# Verification_system_schematics.net
KiCad netlist of a schematic drawn in EasyEDA
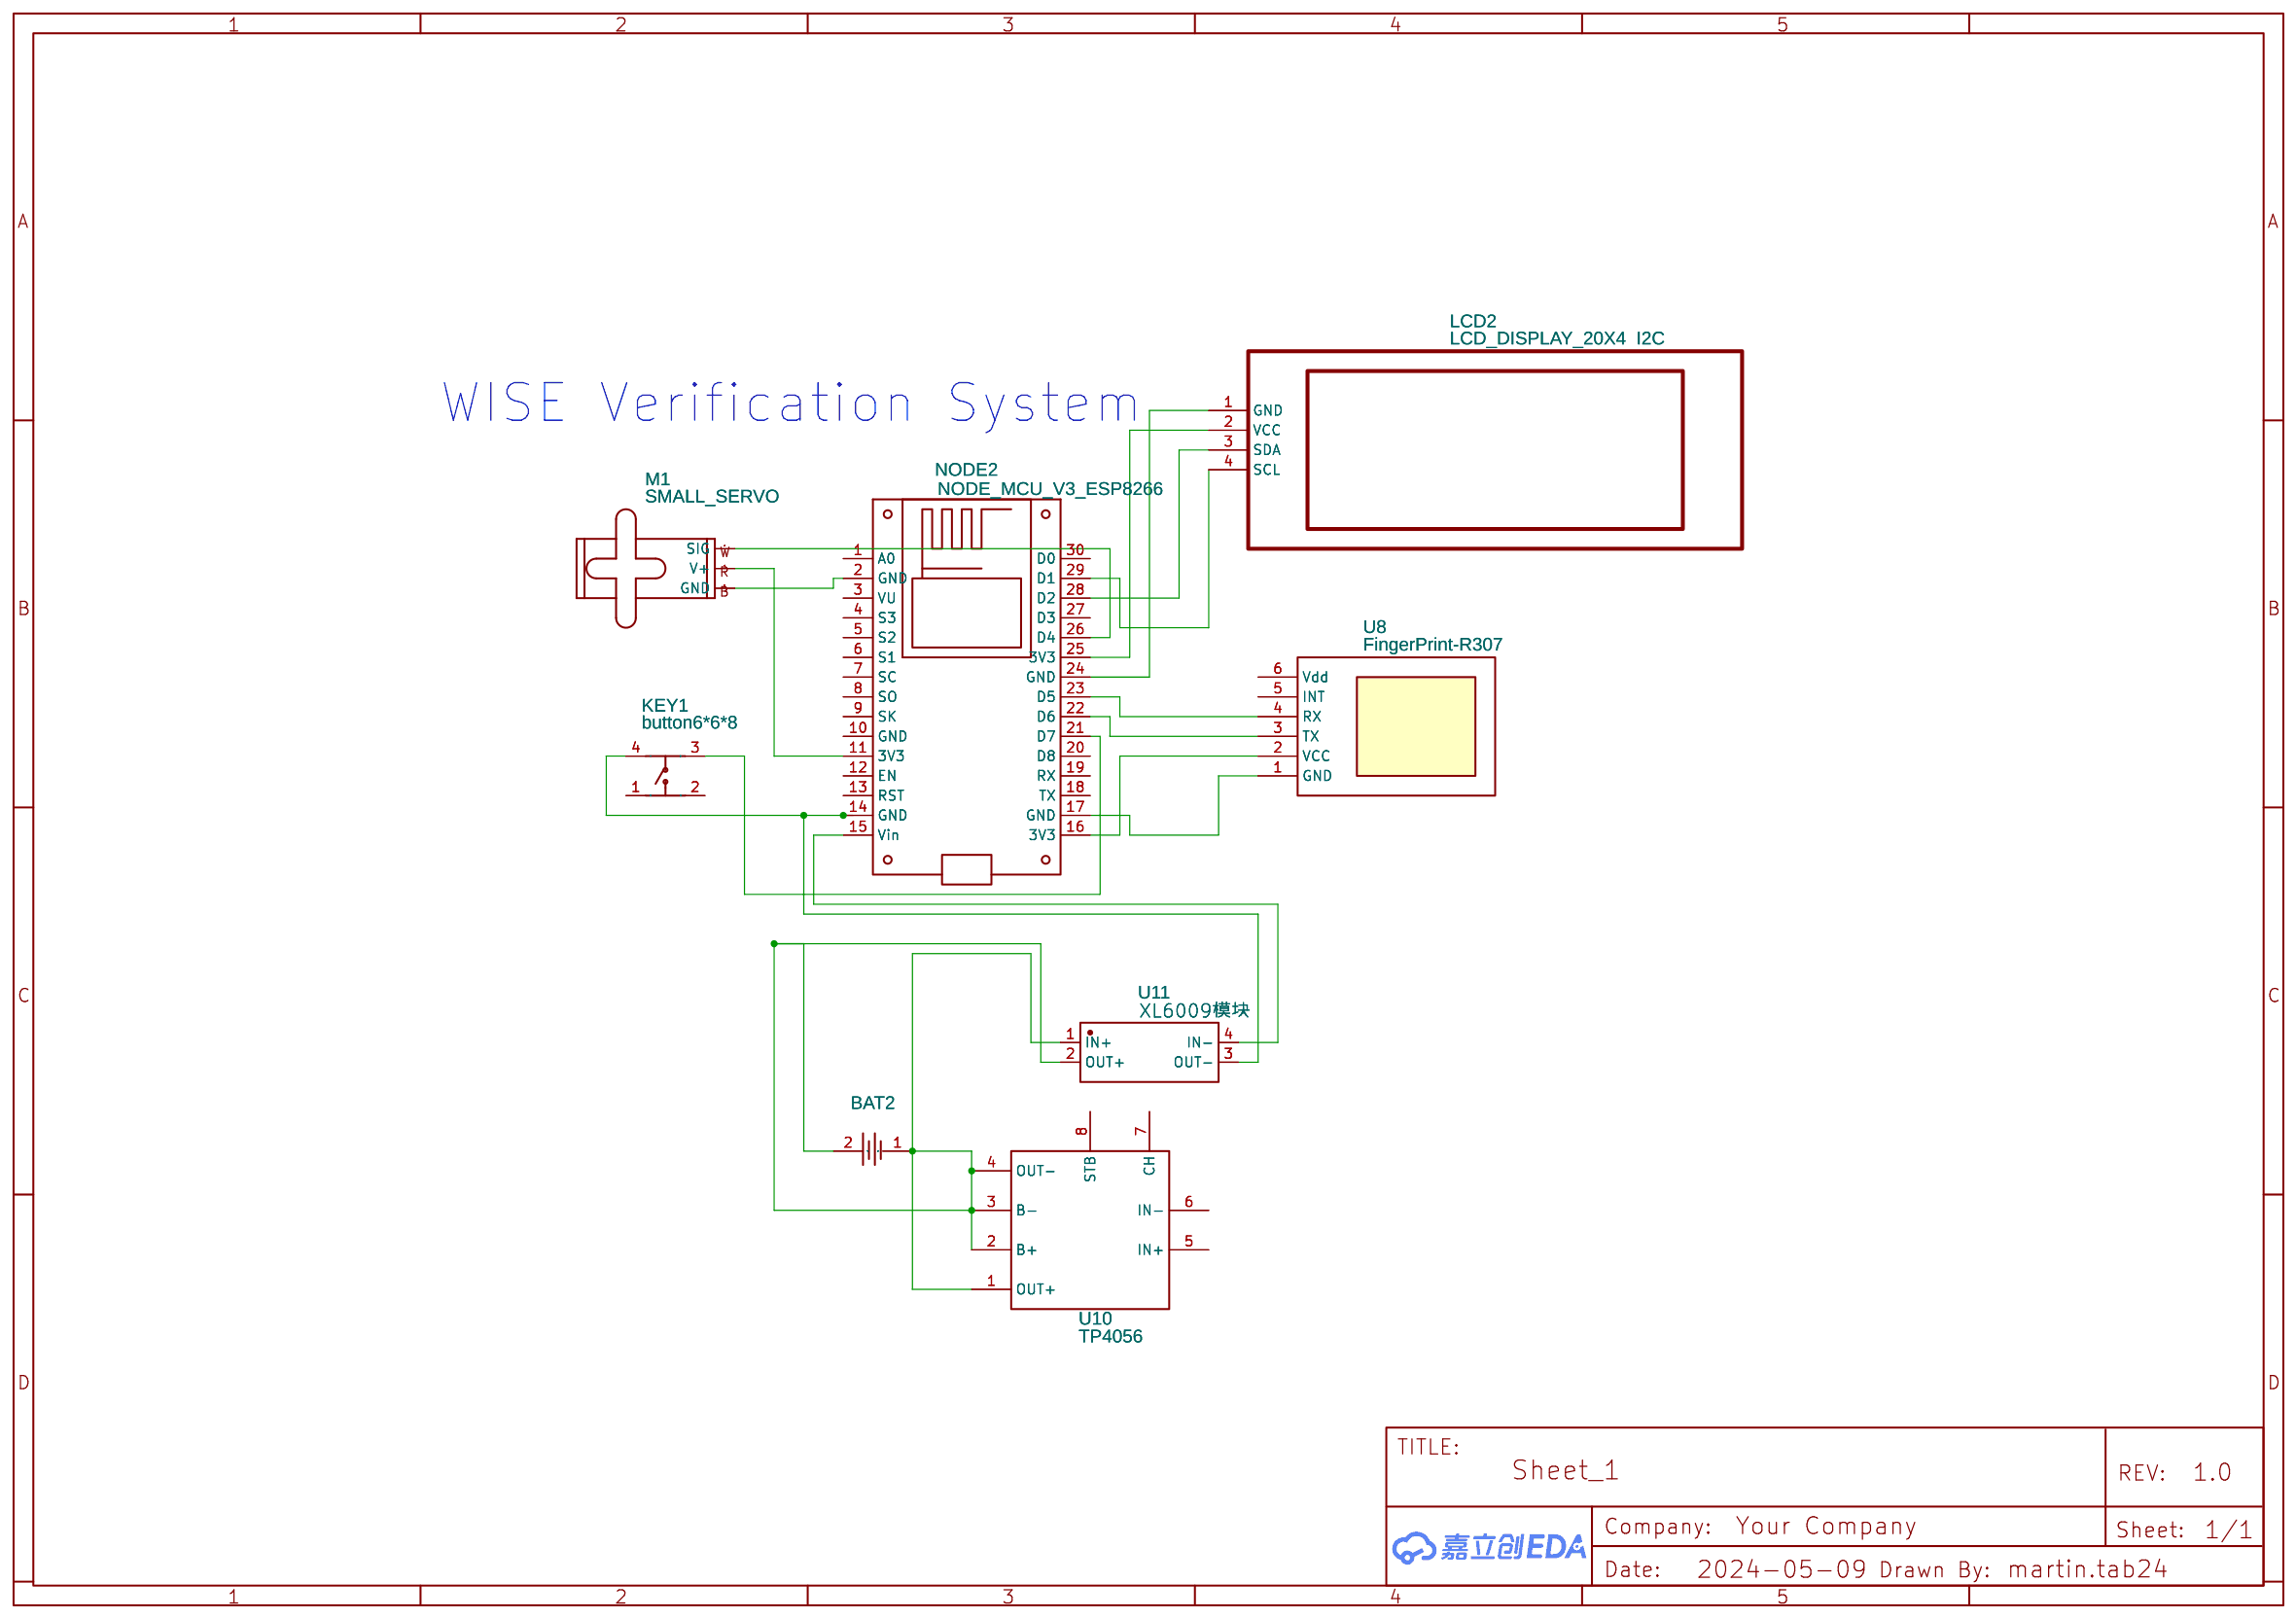
[diagram p0: schematic sheet]

(export (version "E")
  (design (tool "Eeschema 10.0.6"))
  (components
    (comp (ref "BAT2")
      (value "BH-18650-B6AA002")
      (fields (field (name "Manufacturer") "MYOUNG(美阳)"))
      (libsource (lib "") (part "BH-18650-B6AA002"))
    )
    (comp (ref "KEY1")
      (value "button6*6*8")
      (fields (field (name "Manufacturer") "ReliaPro"))
      (libsource (lib "") (part "button6*6*8"))
    )
    (comp (ref "LCD2") (value "LCD_DISPLAY_20X4  I2C") (libsource (lib "") (part "LCD_DISPLAY_20X4  I2C")))
    (comp (ref "M1") (value "SMALL_SERVO") (libsource (lib "") (part "SMALL_SERVO")))
    (comp (ref "NODE2") (value "NODE_MCU_V3_ESP8266") (libsource (lib "") (part "NODE_MCU_V3_ESP8266")))
    (comp (ref "U8")
      (value "FingerPrint-R307")
      (fields (field (name "Manufacturer Part") "R307"))
      (libsource (lib "") (part "FingerPrint-R307"))
    )
    (comp (ref "U10")
      (value "TP4056")
      (fields (field (name "BOM_Manufacturer Part") "New SchematicLib"))
      (libsource (lib "") (part "TP4056"))
    )
    (comp (ref "U11")
      (value "XL6009模块")
      (fields (field (name "Manufacturer Part") "xl6009模块"))
      (libsource (lib "") (part "XL6009模块"))
    )
  )
  (nets
    (net (code "1") (name "Net-(LCD2-GND)") (class "Default")
      (node (ref "LCD2") (pin "1") (pinfunction "GND_1") (pintype "passive"))
      (node (ref "NODE2") (pin "24") (pinfunction "GND_24") (pintype "unspecified"))
    )
    (net (code "2") (name "Net-(LCD2-SCL)") (class "Default")
      (node (ref "LCD2") (pin "4") (pinfunction "SCL_4") (pintype "passive"))
      (node (ref "NODE2") (pin "29") (pinfunction "D1_29") (pintype "unspecified"))
    )
    (net (code "3") (name "Net-(LCD2-SDA)") (class "Default")
      (node (ref "LCD2") (pin "3") (pinfunction "SDA_3") (pintype "passive"))
      (node (ref "NODE2") (pin "28") (pinfunction "D2_28") (pintype "unspecified"))
    )
    (net (code "4") (name "Net-(LCD2-VCC)") (class "Default")
      (node (ref "LCD2") (pin "2") (pinfunction "VCC_2") (pintype "passive"))
      (node (ref "NODE2") (pin "25") (pinfunction "3V3_25") (pintype "unspecified"))
    )
    (net (code "5") (name "Net-(M1-GND)") (class "Default")
      (node (ref "M1") (pin "3") (pinfunction "GND_3") (pintype "unspecified"))
      (node (ref "NODE2") (pin "2") (pinfunction "GND_2") (pintype "unspecified"))
    )
    (net (code "6") (name "Net-(M1-SIG)") (class "Default")
      (node (ref "M1") (pin "1") (pinfunction "SIG_1") (pintype "unspecified"))
      (node (ref "NODE2") (pin "26") (pinfunction "D4_26") (pintype "unspecified"))
    )
    (net (code "7") (name "Net-(M1-V+)") (class "Default")
      (node (ref "M1") (pin "2") (pinfunction "V+_2") (pintype "unspecified"))
      (node (ref "NODE2") (pin "11") (pinfunction "3V3_11") (pintype "unspecified"))
    )
    (net (code "8") (name "Net-(NODE2-D5)") (class "Default")
      (node (ref "NODE2") (pin "23") (pinfunction "D5_23") (pintype "unspecified"))
      (node (ref "U8") (pin "4") (pinfunction "RX_4") (pintype "unspecified"))
    )
    (net (code "9") (name "Net-(NODE2-D6)") (class "Default")
      (node (ref "NODE2") (pin "22") (pinfunction "D6_22") (pintype "unspecified"))
      (node (ref "U8") (pin "3") (pinfunction "TX_3") (pintype "unspecified"))
    )
    (net (code "10") (name "Net-(NODE2-D7)") (class "Default")
      (node (ref "KEY1") (pin "3") (pinfunction "3_3") (pintype "unspecified"))
      (node (ref "NODE2") (pin "21") (pinfunction "D7_21") (pintype "unspecified"))
    )
    (net (code "11") (name "Net-(NODE2-Vin)") (class "Default")
      (node (ref "NODE2") (pin "15") (pinfunction "Vin_15") (pintype "unspecified"))
      (node (ref "U11") (pin "4") (pinfunction "IN-_4") (pintype "unspecified"))
    )
    (net (code "12") (name "Net-(U8-GND)") (class "Default")
      (node (ref "NODE2") (pin "17") (pinfunction "GND_17") (pintype "unspecified"))
      (node (ref "U8") (pin "1") (pinfunction "GND_1") (pintype "unspecified"))
    )
    (net (code "13") (name "Net-(U8-VCC)") (class "Default")
      (node (ref "NODE2") (pin "16") (pinfunction "3V3_16") (pintype "unspecified"))
      (node (ref "U8") (pin "2") (pinfunction "VCC_2") (pintype "unspecified"))
    )
    (net (code "14") (name "Net-(U10-B+)") (class "Default")
      (node (ref "BAT2") (pin "1") (pinfunction "1_1") (pintype "input"))
      (node (ref "BAT2") (pin "2") (pinfunction "2_2") (pintype "input"))
      (node (ref "U10") (pin "1") (pinfunction "OUT+_1") (pintype "unspecified"))
      (node (ref "U10") (pin "2") (pinfunction "B+_2") (pintype "unspecified"))
      (node (ref "U10") (pin "3") (pinfunction "B-_3") (pintype "unspecified"))
      (node (ref "U10") (pin "4") (pinfunction "OUT-_4") (pintype "unspecified"))
      (node (ref "U11") (pin "1") (pinfunction "IN+_1") (pintype "unspecified"))
      (node (ref "U11") (pin "2") (pinfunction "OUT+_2") (pintype "unspecified"))
    )
    (net (code "15") (name "Net-(U11-OUT-)") (class "Default")
      (node (ref "KEY1") (pin "4") (pinfunction "4_4") (pintype "unspecified"))
      (node (ref "NODE2") (pin "14") (pinfunction "GND_14") (pintype "unspecified"))
      (node (ref "U11") (pin "3") (pinfunction "OUT-_3") (pintype "unspecified"))
    )
    (net (code "16") (name "unconnected-(KEY1-Pad1)") (class "Default")
      (node (ref "KEY1") (pin "1") (pinfunction "1_1") (pintype "unspecified"))
    )
    (net (code "17") (name "unconnected-(KEY1-Pad2)") (class "Default")
      (node (ref "KEY1") (pin "2") (pinfunction "2_2") (pintype "unspecified"))
    )
    (net (code "18") (name "unconnected-(NODE2-A0-Pad1)") (class "Default")
      (node (ref "NODE2") (pin "1") (pinfunction "A0_1") (pintype "unspecified"))
    )
    (net (code "19") (name "unconnected-(NODE2-D0-Pad30)") (class "Default")
      (node (ref "NODE2") (pin "30") (pinfunction "D0_30") (pintype "unspecified"))
    )
    (net (code "20") (name "unconnected-(NODE2-D3-Pad27)") (class "Default")
      (node (ref "NODE2") (pin "27") (pinfunction "D3_27") (pintype "unspecified"))
    )
    (net (code "21") (name "unconnected-(NODE2-D8-Pad20)") (class "Default")
      (node (ref "NODE2") (pin "20") (pinfunction "D8_20") (pintype "unspecified"))
    )
    (net (code "22") (name "unconnected-(NODE2-EN-Pad12)") (class "Default")
      (node (ref "NODE2") (pin "12") (pinfunction "EN_12") (pintype "unspecified"))
    )
    (net (code "23") (name "unconnected-(NODE2-GND-Pad10)") (class "Default")
      (node (ref "NODE2") (pin "10") (pinfunction "GND_10") (pintype "unspecified"))
    )
    (net (code "24") (name "unconnected-(NODE2-RST-Pad13)") (class "Default")
      (node (ref "NODE2") (pin "13") (pinfunction "RST_13") (pintype "unspecified"))
    )
    (net (code "25") (name "unconnected-(NODE2-RX-Pad19)") (class "Default")
      (node (ref "NODE2") (pin "19") (pinfunction "RX_19") (pintype "unspecified"))
    )
    (net (code "26") (name "unconnected-(NODE2-S1-Pad6)") (class "Default")
      (node (ref "NODE2") (pin "6") (pinfunction "S1_6") (pintype "unspecified"))
    )
    (net (code "27") (name "unconnected-(NODE2-S2-Pad5)") (class "Default")
      (node (ref "NODE2") (pin "5") (pinfunction "S2_5") (pintype "unspecified"))
    )
    (net (code "28") (name "unconnected-(NODE2-S3-Pad4)") (class "Default")
      (node (ref "NODE2") (pin "4") (pinfunction "S3_4") (pintype "unspecified"))
    )
    (net (code "29") (name "unconnected-(NODE2-SC-Pad7)") (class "Default")
      (node (ref "NODE2") (pin "7") (pinfunction "SC_7") (pintype "unspecified"))
    )
    (net (code "30") (name "unconnected-(NODE2-SK-Pad9)") (class "Default")
      (node (ref "NODE2") (pin "9") (pinfunction "SK_9") (pintype "unspecified"))
    )
    (net (code "31") (name "unconnected-(NODE2-SO-Pad8)") (class "Default")
      (node (ref "NODE2") (pin "8") (pinfunction "SO_8") (pintype "unspecified"))
    )
    (net (code "32") (name "unconnected-(NODE2-TX-Pad18)") (class "Default")
      (node (ref "NODE2") (pin "18") (pinfunction "TX_18") (pintype "unspecified"))
    )
    (net (code "33") (name "unconnected-(NODE2-VU-Pad3)") (class "Default")
      (node (ref "NODE2") (pin "3") (pinfunction "VU_3") (pintype "unspecified"))
    )
    (net (code "34") (name "unconnected-(U8-INT-Pad5)") (class "Default")
      (node (ref "U8") (pin "5") (pinfunction "INT_5") (pintype "unspecified"))
    )
    (net (code "35") (name "unconnected-(U8-Vdd-Pad6)") (class "Default")
      (node (ref "U8") (pin "6") (pinfunction "Vdd_6") (pintype "unspecified"))
    )
    (net (code "36") (name "unconnected-(U10-CH-Pad7)") (class "Default")
      (node (ref "U10") (pin "7") (pinfunction "CH_7") (pintype "unspecified"))
    )
    (net (code "37") (name "unconnected-(U10-IN+-Pad5)") (class "Default")
      (node (ref "U10") (pin "5") (pinfunction "IN+_5") (pintype "unspecified"))
    )
    (net (code "38") (name "unconnected-(U10-IN--Pad6)") (class "Default")
      (node (ref "U10") (pin "6") (pinfunction "IN-_6") (pintype "unspecified"))
    )
    (net (code "39") (name "unconnected-(U10-STB-Pad8)") (class "Default")
      (node (ref "U10") (pin "8") (pinfunction "STB_8") (pintype "unspecified"))
    )
  )
)
